# OMD_CAN_VERT.net
KiCad netlist of a schematic drawn in Altium Designer
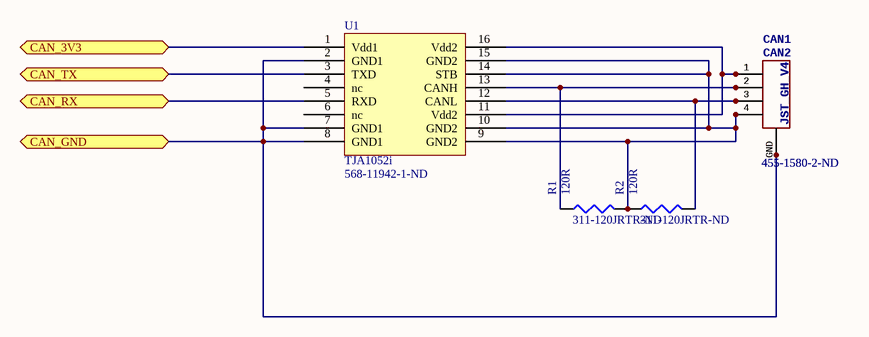
[diagram p0: OMD_CAN_VERT.SchDoc]

(export (version "E")
  (design (tool "Eeschema 10.0.6"))
  (components
    (comp (ref "CAN1")
      (value "JST_GH_V4")
      (footprint "JST_GH_V4")
      (description "BM04B-GHS-TBT")
      (fields (field (name "SUPPLIER PART NUMBER 1") "455-1580-2-ND"))
      (libsource (lib "CB_SCI_AERO") (part "JST_GH_V4"))
    )
    (comp (ref "CAN2")
      (value "JST_GH_V4")
      (footprint "JST_GH_V4")
      (description "BM04B-GHS-TBT")
      (fields (field (name "SUPPLIER PART NUMBER 1") "455-1580-2-ND"))
      (libsource (lib "CB_SCI_AERO") (part "JST_GH_V4"))
    )
    (comp (ref "R1")
      (value "120R")
      (footprint "R0402")
      (description "RES SMD 120 OHM 5% 1/16W 0402")
      (fields (field (name "SUPPLIER PART NUMBER 1") "311-120JRTR-ND"))
      (libsource (lib "OMD") (part "Resistor"))
    )
    (comp (ref "R2")
      (value "120R")
      (footprint "R0402")
      (description "RES SMD 120 OHM 5% 1/16W 0402")
      (fields (field (name "SUPPLIER PART NUMBER 1") "311-120JRTR-ND"))
      (libsource (lib "OMD") (part "Resistor"))
    )
    (comp (ref "U1")
      (value "TJA1052i")
      (footprint "TJA1052i")
      (fields (field (name "SUPPLIER PART NUMBER 1") "568-11942-1-ND"))
      (libsource (lib "OMD") (part "TJA1052i"))
    )
  )
  (nets
    (net (code "1") (name "/CAN_3V3") (class "Default")
      (node (ref "U1") (pin "1") (pinfunction "Vdd1_1") (pintype "passive"))
    )
    (net (code "2") (name "/CAN_GND") (class "Default")
      (node (ref "CAN1") (pin "GND") (pinfunction "GND_GND") (pintype "passive"))
      (node (ref "CAN2") (pin "GND") (pinfunction "GND_GND") (pintype "passive"))
      (node (ref "U1") (pin "2") (pinfunction "GND1_2") (pintype "passive"))
      (node (ref "U1") (pin "7") (pinfunction "GND1_7") (pintype "passive"))
      (node (ref "U1") (pin "8") (pinfunction "GND1_8") (pintype "passive"))
    )
    (net (code "3") (name "/CAN_RX") (class "Default")
      (node (ref "U1") (pin "5") (pinfunction "RXD_5") (pintype "passive"))
    )
    (net (code "4") (name "/CAN_TX") (class "Default")
      (node (ref "U1") (pin "3") (pinfunction "TXD_3") (pintype "passive"))
    )
    (net (code "5") (name "Net-(CAN1-Pad1)") (class "Default")
      (node (ref "CAN1") (pin "1") (pinfunction "1_1") (pintype "passive"))
      (node (ref "CAN2") (pin "1") (pinfunction "1_1") (pintype "passive"))
      (node (ref "U1") (pin "11") (pinfunction "Vdd2_11") (pintype "passive"))
      (node (ref "U1") (pin "16") (pinfunction "Vdd2_16") (pintype "passive"))
    )
    (net (code "6") (name "Net-(U1-CANH)") (class "Default")
      (node (ref "CAN1") (pin "2") (pinfunction "2_2") (pintype "passive"))
      (node (ref "CAN2") (pin "2") (pinfunction "2_2") (pintype "passive"))
      (node (ref "R1") (pin "1") (pinfunction "1_1") (pintype "passive"))
      (node (ref "U1") (pin "13") (pinfunction "CANH_13") (pintype "passive"))
    )
    (net (code "7") (name "Net-(U1-CANL)") (class "Default")
      (node (ref "CAN1") (pin "3") (pinfunction "3_3") (pintype "passive"))
      (node (ref "CAN2") (pin "3") (pinfunction "3_3") (pintype "passive"))
      (node (ref "R2") (pin "2") (pinfunction "2_2") (pintype "passive"))
      (node (ref "U1") (pin "12") (pinfunction "CANL_12") (pintype "passive"))
    )
    (net (code "8") (name "Net-(U1-STB)") (class "Default")
      (node (ref "CAN1") (pin "4") (pinfunction "4_4") (pintype "passive"))
      (node (ref "CAN2") (pin "4") (pinfunction "4_4") (pintype "passive"))
      (node (ref "R1") (pin "2") (pinfunction "2_2") (pintype "passive"))
      (node (ref "R2") (pin "1") (pinfunction "1_1") (pintype "passive"))
      (node (ref "U1") (pin "10") (pinfunction "GND2_10") (pintype "passive"))
      (node (ref "U1") (pin "14") (pinfunction "STB_14") (pintype "passive"))
      (node (ref "U1") (pin "15") (pinfunction "GND2_15") (pintype "passive"))
      (node (ref "U1") (pin "9") (pinfunction "GND2_9") (pintype "passive"))
    )
    (net (code "9") (name "unconnected-(U1-nc-Pad4)") (class "Default")
      (node (ref "U1") (pin "4") (pinfunction "nc_4") (pintype "passive"))
    )
    (net (code "10") (name "unconnected-(U1-nc-Pad6)") (class "Default")
      (node (ref "U1") (pin "6") (pinfunction "nc_6") (pintype "passive"))
    )
  )
)
